# zx-SD-Card_SPI.net
KiCad netlist of a schematic drawn in Altium Designer
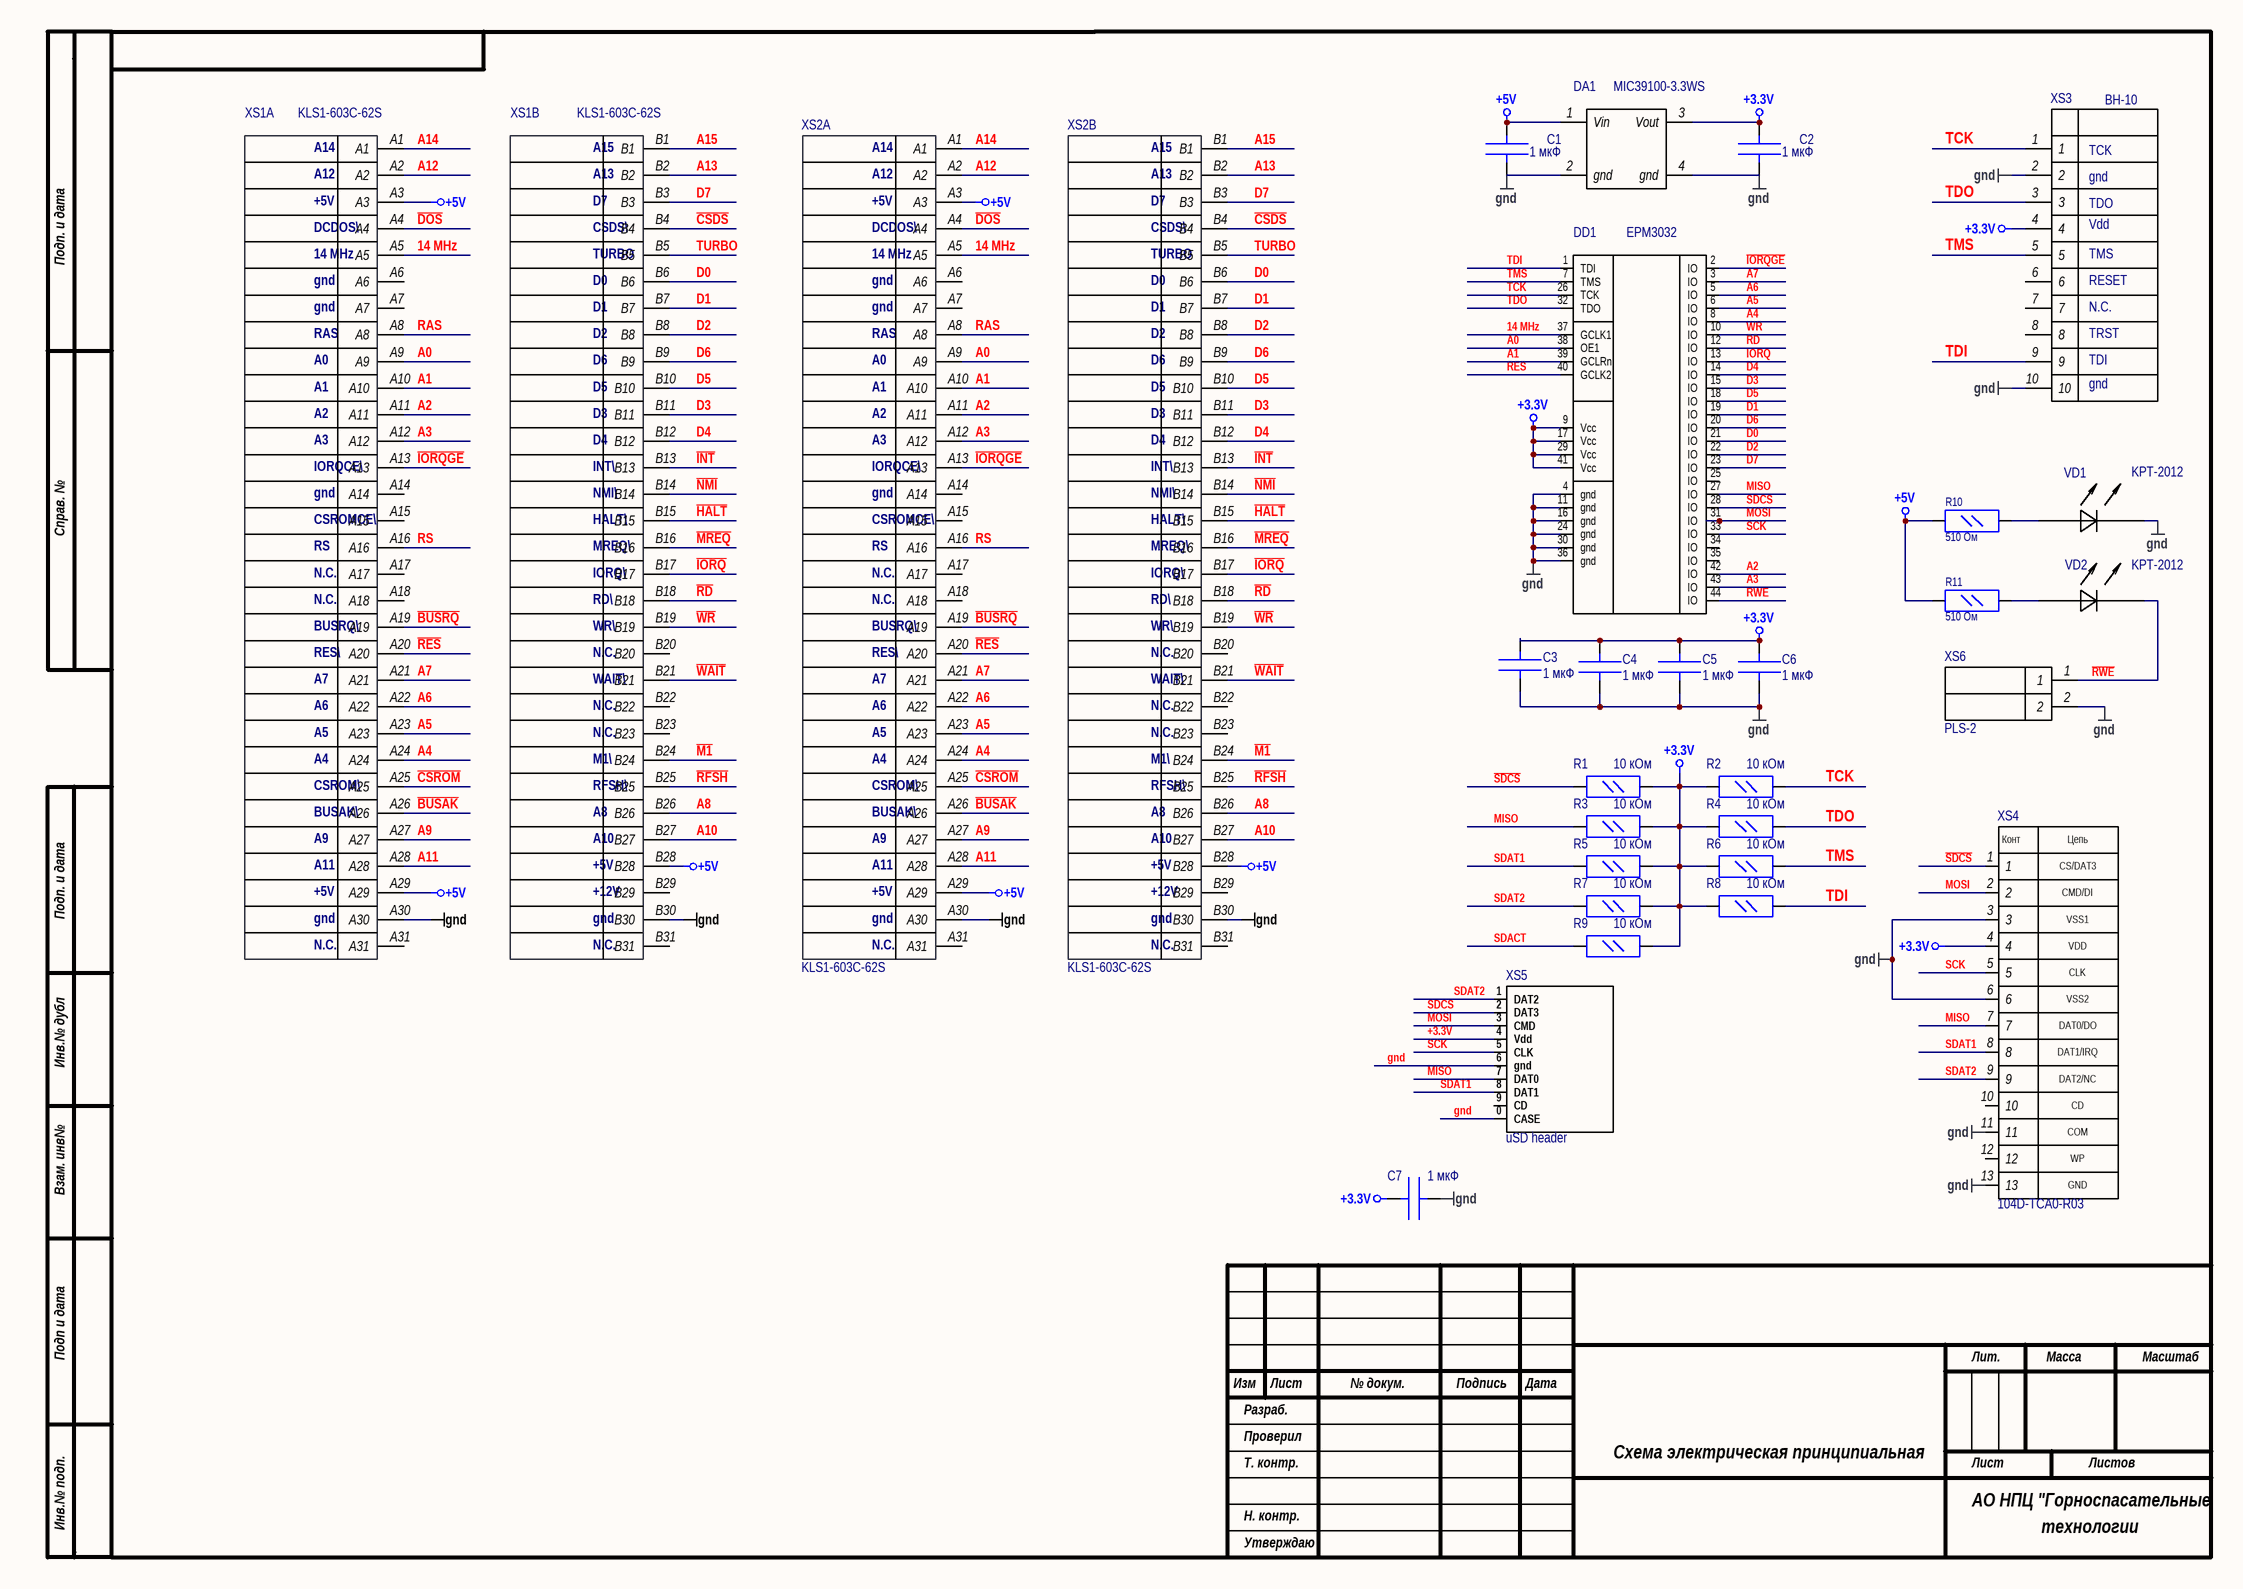
[diagram p0: zx-SD-Card_SPI.SchDoc]

(export (version "E")
  (design (tool "Eeschema 10.0.6"))
  (components
    (comp (ref "C1")
      (value "1 мкФ")
      (footprint "CAP C 3216 (1206) 1.9h")
      (description "Конденсатор не полярный")
      (fields (field (name "PART NUMBER") "CC1206KKX5R9BB105") (field (name "VOLTAGE") "50"))
      (libsource (lib "Capacitor_chip 1206$") (part "ЧИП-1206-X5R-1 мкФ 50В ±10%"))
    )
    (comp (ref "C2")
      (value "1 мкФ")
      (footprint "CAP C 3216 (1206) 1.9h")
      (description "Конденсатор не полярный")
      (fields (field (name "PART NUMBER") "CC1206KKX5R9BB105") (field (name "VOLTAGE") "50"))
      (libsource (lib "Capacitor_chip 1206$") (part "ЧИП-1206-X5R-1 мкФ 50В ±10%"))
    )
    (comp (ref "C3")
      (value "1 мкФ")
      (footprint "CAP C 2012 (0805) 1.45h")
      (description "Конденсатор не полярный")
      (fields (field (name "PART NUMBER") "CC0805KKX5R9BB105") (field (name "VOLTAGE") "50"))
      (libsource (lib "Capacitor_chip 0805$") (part "ЧИП-0805-X5R-1 мкФ 50В ±10%"))
    )
    (comp (ref "C4")
      (value "1 мкФ")
      (footprint "CAP C 2012 (0805) 1.45h")
      (description "Конденсатор не полярный")
      (fields (field (name "PART NUMBER") "CC0805KKX5R9BB105") (field (name "VOLTAGE") "50"))
      (libsource (lib "Capacitor_chip 0805$") (part "ЧИП-0805-X5R-1 мкФ 50В ±10%"))
    )
    (comp (ref "C5")
      (value "1 мкФ")
      (footprint "CAP C 2012 (0805) 1.45h")
      (description "Конденсатор не полярный")
      (fields (field (name "PART NUMBER") "CC0805KKX5R9BB105") (field (name "VOLTAGE") "50"))
      (libsource (lib "Capacitor_chip 0805$") (part "ЧИП-0805-X5R-1 мкФ 50В ±10%"))
    )
    (comp (ref "C6")
      (value "1 мкФ")
      (footprint "CAP C 2012 (0805) 1.45h")
      (description "Конденсатор не полярный")
      (fields (field (name "PART NUMBER") "CC0805KKX5R9BB105") (field (name "VOLTAGE") "50"))
      (libsource (lib "Capacitor_chip 0805$") (part "ЧИП-0805-X5R-1 мкФ 50В ±10%"))
    )
    (comp (ref "C7")
      (value "1 мкФ")
      (footprint "CAP C 2012 (0805) 1.45h")
      (description "Конденсатор не полярный")
      (fields (field (name "PART NUMBER") "CC0805KKX5R9BB105") (field (name "VOLTAGE") "50"))
      (libsource (lib "Capacitor_chip 0805$") (part "ЧИП-0805-X5R-1 мкФ 50В ±10%"))
    )
    (comp (ref "DA1")
      (value "MIC39100-3.3WS")
      (footprint "MIC39100-3.3WS")
      (description "LDO 3.3V 1A")
      (libsource (lib "ipa") (part "MIC39100-3.3WS"))
    )
    (comp (ref "DD1") (value "EPM3032") (footprint "ALTERA TQFP-44") (libsource (lib "gst") (part "EPM3032")))
    (comp (ref "R1")
      (value "10 кОм")
      (footprint "RES C 2012 (0805) 0.65h")
      (description "Резистор 0.125 Вт")
      (fields (field (name "PART NUMBER") "RC0805FR-0710KL") (field (name "TOLERANCE") "±1%"))
      (libsource (lib "Resistor_chip 0805$") (part "ЧИП-0805-10 кОм ±1%"))
    )
    (comp (ref "R2")
      (value "10 кОм")
      (footprint "RES C 2012 (0805) 0.65h")
      (description "Резистор 0.125 Вт")
      (fields (field (name "PART NUMBER") "RC0805FR-0710KL") (field (name "TOLERANCE") "±1%"))
      (libsource (lib "Resistor_chip 0805$") (part "ЧИП-0805-10 кОм ±1%"))
    )
    (comp (ref "R3")
      (value "10 кОм")
      (footprint "RES C 2012 (0805) 0.65h")
      (description "Резистор 0.125 Вт")
      (fields (field (name "PART NUMBER") "RC0805FR-0710KL") (field (name "TOLERANCE") "±1%"))
      (libsource (lib "Resistor_chip 0805$") (part "ЧИП-0805-10 кОм ±1%"))
    )
    (comp (ref "R4")
      (value "10 кОм")
      (footprint "RES C 2012 (0805) 0.65h")
      (description "Резистор 0.125 Вт")
      (fields (field (name "PART NUMBER") "RC0805FR-0710KL") (field (name "TOLERANCE") "±1%"))
      (libsource (lib "Resistor_chip 0805$") (part "ЧИП-0805-10 кОм ±1%"))
    )
    (comp (ref "R5")
      (value "10 кОм")
      (footprint "RES C 2012 (0805) 0.65h")
      (description "Резистор 0.125 Вт")
      (fields (field (name "PART NUMBER") "RC0805FR-0710KL") (field (name "TOLERANCE") "±1%"))
      (libsource (lib "Resistor_chip 0805$") (part "ЧИП-0805-10 кОм ±1%"))
    )
    (comp (ref "R6")
      (value "10 кОм")
      (footprint "RES C 2012 (0805) 0.65h")
      (description "Резистор 0.125 Вт")
      (fields (field (name "PART NUMBER") "RC0805FR-0710KL") (field (name "TOLERANCE") "±1%"))
      (libsource (lib "Resistor_chip 0805$") (part "ЧИП-0805-10 кОм ±1%"))
    )
    (comp (ref "R7")
      (value "10 кОм")
      (footprint "RES C 2012 (0805) 0.65h")
      (description "Резистор 0.125 Вт")
      (fields (field (name "PART NUMBER") "RC0805FR-0710KL") (field (name "TOLERANCE") "±1%"))
      (libsource (lib "Resistor_chip 0805$") (part "ЧИП-0805-10 кОм ±1%"))
    )
    (comp (ref "R8")
      (value "10 кОм")
      (footprint "RES C 2012 (0805) 0.65h")
      (description "Резистор 0.125 Вт")
      (fields (field (name "PART NUMBER") "RC0805FR-0710KL") (field (name "TOLERANCE") "±1%"))
      (libsource (lib "Resistor_chip 0805$") (part "ЧИП-0805-10 кОм ±1%"))
    )
    (comp (ref "R9")
      (value "10 кОм")
      (footprint "RES C 2012 (0805) 0.65h")
      (description "Резистор 0.125 Вт")
      (fields (field (name "PART NUMBER") "RC0805FR-0710KL") (field (name "TOLERANCE") "±1%"))
      (libsource (lib "Resistor_chip 0805$") (part "ЧИП-0805-10 кОм ±1%"))
    )
    (comp (ref "R10")
      (value "510 Ом")
      (footprint "RES C 2012 (0805) 0.65h")
      (description "Резистор 0.125 Вт")
      (fields (field (name "PART NUMBER") "RC0805JR-07510RL") (field (name "TOLERANCE") "±5%"))
      (libsource (lib "Resistor_chip 0805$") (part "ЧИП-0805-510 Ом ±5%"))
    )
    (comp (ref "R11")
      (value "510 Ом")
      (footprint "RES C 2012 (0805) 0.65h")
      (description "Резистор 0.125 Вт")
      (fields (field (name "PART NUMBER") "RC0805JR-07510RL") (field (name "TOLERANCE") "±5%"))
      (libsource (lib "Resistor_chip 0805$") (part "ЧИП-0805-510 Ом ±5%"))
    )
    (comp (ref "VD1") (value "KPT-2012") (footprint "KPT-2012") (libsource (lib "ipa") (part "KPT-2012")))
    (comp (ref "VD2") (value "KPT-2012") (footprint "KPT-2012") (libsource (lib "ipa") (part "KPT-2012")))
    (comp (ref "XS1")
      (value "KLS1-603C-62S")
      (footprint "KLS1-603 ISA")
      (libsource (lib "gst") (part "KLS1-603C-64S"))
    )
    (comp (ref "XS2")
      (value "KLS1-603C-62S")
      (footprint "KLS1-603C-64S")
      (libsource (lib "gst") (part "KLS1-603C-64S"))
    )
    (comp (ref "XS3") (value "BH-10") (footprint "BH-10") (libsource (lib "ipa") (part "AVR_ISP_JTAG")))
    (comp (ref "XS4")
      (value "104D-TCA0-R03")
      (footprint "104D-TCA0-R03")
      (fields (field (name "MANUFACTURER") "Attend technology"))
      (libsource (lib "Connector$") (part "104D-TCA0-R03"))
    )
    (comp (ref "XS5")
      (value "uSD header")
      (footprint "uSD")
      (description "uSD")
      (libsource (lib "gst") (part "uSD"))
    )
    (comp (ref "XS6") (value "PLS-2") (footprint "PLS-2") (libsource (lib "ipa") (part "PLS-2")))
  )
  (nets
    (net (code "1") (name "+3.3V") (class "Default")
      (node (ref "C2") (pin "2") (pinfunction "2_2") (pintype "passive"))
      (node (ref "C3") (pin "1") (pinfunction "1_1") (pintype "passive"))
      (node (ref "C4") (pin "1") (pinfunction "1_1") (pintype "passive"))
      (node (ref "C5") (pin "1") (pinfunction "1_1") (pintype "passive"))
      (node (ref "C6") (pin "1") (pinfunction "1_1") (pintype "passive"))
      (node (ref "C7") (pin "1") (pinfunction "1_1") (pintype "passive"))
      (node (ref "DA1") (pin "3") (pinfunction "Vout_3") (pintype "passive"))
      (node (ref "DD1") (pin "17") (pinfunction "Vcc_17") (pintype "passive"))
      (node (ref "DD1") (pin "29") (pinfunction "Vcc_29") (pintype "passive"))
      (node (ref "DD1") (pin "41") (pinfunction "Vcc_41") (pintype "passive"))
      (node (ref "DD1") (pin "9") (pinfunction "Vcc_9") (pintype "passive"))
      (node (ref "R1") (pin "2") (pinfunction "2_2") (pintype "passive"))
      (node (ref "R2") (pin "1") (pinfunction "1_1") (pintype "passive"))
      (node (ref "R3") (pin "2") (pinfunction "2_2") (pintype "passive"))
      (node (ref "R4") (pin "1") (pinfunction "1_1") (pintype "passive"))
      (node (ref "R5") (pin "2") (pinfunction "2_2") (pintype "passive"))
      (node (ref "R6") (pin "1") (pinfunction "1_1") (pintype "passive"))
      (node (ref "R7") (pin "2") (pinfunction "2_2") (pintype "passive"))
      (node (ref "R8") (pin "1") (pinfunction "1_1") (pintype "passive"))
      (node (ref "R9") (pin "2") (pinfunction "2_2") (pintype "passive"))
      (node (ref "XS3") (pin "4") (pinfunction "4_4") (pintype "passive"))
      (node (ref "XS4") (pin "4") (pinfunction "4_4") (pintype "passive"))
      (node (ref "XS5") (pin "4") (pinfunction "Vdd_4") (pintype "passive"))
    )
    (net (code "2") (name "+5V") (class "Default")
      (node (ref "C1") (pin "2") (pinfunction "2_2") (pintype "passive"))
      (node (ref "DA1") (pin "1") (pinfunction "Vin_1") (pintype "passive"))
      (node (ref "R10") (pin "1") (pinfunction "1_1") (pintype "passive"))
      (node (ref "R11") (pin "1") (pinfunction "1_1") (pintype "passive"))
      (node (ref "XS1") (pin "A29") (pinfunction "A29_A29") (pintype "passive"))
      (node (ref "XS1") (pin "A3") (pinfunction "A3_A3") (pintype "passive"))
      (node (ref "XS1") (pin "B28") (pinfunction "B28_B28") (pintype "passive"))
      (node (ref "XS2") (pin "A29") (pinfunction "A29_A29") (pintype "passive"))
      (node (ref "XS2") (pin "A3") (pinfunction "A3_A3") (pintype "passive"))
      (node (ref "XS2") (pin "B28") (pinfunction "B28_B28") (pintype "passive"))
    )
    (net (code "3") (name "/14 MHz") (class "Default")
      (node (ref "DD1") (pin "37") (pinfunction "GCLK1_37") (pintype "passive"))
      (node (ref "XS1") (pin "A5") (pinfunction "A5_A5") (pintype "passive"))
      (node (ref "XS2") (pin "A5") (pinfunction "A5_A5") (pintype "passive"))
    )
    (net (code "4") (name "/A0") (class "Default")
      (node (ref "DD1") (pin "38") (pinfunction "OE1_38") (pintype "passive"))
      (node (ref "XS1") (pin "A9") (pinfunction "A9_A9") (pintype "passive"))
      (node (ref "XS2") (pin "A9") (pinfunction "A9_A9") (pintype "passive"))
    )
    (net (code "5") (name "/A1") (class "Default")
      (node (ref "DD1") (pin "39") (pinfunction "GCLRn_39") (pintype "passive"))
      (node (ref "XS1") (pin "A10") (pinfunction "A10_A10") (pintype "passive"))
      (node (ref "XS2") (pin "A10") (pinfunction "A10_A10") (pintype "passive"))
    )
    (net (code "6") (name "/A2") (class "Default")
      (node (ref "DD1") (pin "42") (pinfunction "IO_42") (pintype "passive"))
      (node (ref "XS1") (pin "A11") (pinfunction "A11_A11") (pintype "passive"))
      (node (ref "XS2") (pin "A11") (pinfunction "A11_A11") (pintype "passive"))
    )
    (net (code "7") (name "/A3") (class "Default")
      (node (ref "DD1") (pin "43") (pinfunction "IO_43") (pintype "passive"))
      (node (ref "XS1") (pin "A12") (pinfunction "A12_A12") (pintype "passive"))
      (node (ref "XS2") (pin "A12") (pinfunction "A12_A12") (pintype "passive"))
    )
    (net (code "8") (name "/A4") (class "Default")
      (node (ref "DD1") (pin "8") (pinfunction "IO_8") (pintype "passive"))
      (node (ref "XS1") (pin "A24") (pinfunction "A24_A24") (pintype "passive"))
      (node (ref "XS2") (pin "A24") (pinfunction "A24_A24") (pintype "passive"))
    )
    (net (code "9") (name "/A5") (class "Default")
      (node (ref "DD1") (pin "6") (pinfunction "IO_6") (pintype "passive"))
      (node (ref "XS1") (pin "A23") (pinfunction "A23_A23") (pintype "passive"))
      (node (ref "XS2") (pin "A23") (pinfunction "A23_A23") (pintype "passive"))
    )
    (net (code "10") (name "/A6") (class "Default")
      (node (ref "DD1") (pin "5") (pinfunction "IO_5") (pintype "passive"))
      (node (ref "XS1") (pin "A22") (pinfunction "A22_A22") (pintype "passive"))
      (node (ref "XS2") (pin "A22") (pinfunction "A22_A22") (pintype "passive"))
    )
    (net (code "11") (name "/A7") (class "Default")
      (node (ref "DD1") (pin "3") (pinfunction "IO_3") (pintype "passive"))
      (node (ref "XS1") (pin "A21") (pinfunction "A21_A21") (pintype "passive"))
      (node (ref "XS2") (pin "A21") (pinfunction "A21_A21") (pintype "passive"))
    )
    (net (code "12") (name "/A8") (class "Default")
      (node (ref "XS1") (pin "B26") (pinfunction "B26_B26") (pintype "passive"))
      (node (ref "XS2") (pin "B26") (pinfunction "B26_B26") (pintype "passive"))
    )
    (net (code "13") (name "/A9") (class "Default")
      (node (ref "XS1") (pin "A27") (pinfunction "A27_A27") (pintype "passive"))
      (node (ref "XS2") (pin "A27") (pinfunction "A27_A27") (pintype "passive"))
    )
    (net (code "14") (name "/A10") (class "Default")
      (node (ref "XS1") (pin "B27") (pinfunction "B27_B27") (pintype "passive"))
      (node (ref "XS2") (pin "B27") (pinfunction "B27_B27") (pintype "passive"))
    )
    (net (code "15") (name "/A11") (class "Default")
      (node (ref "XS1") (pin "A28") (pinfunction "A28_A28") (pintype "passive"))
      (node (ref "XS2") (pin "A28") (pinfunction "A28_A28") (pintype "passive"))
    )
    (net (code "16") (name "/A12") (class "Default")
      (node (ref "XS1") (pin "A2") (pinfunction "A2_A2") (pintype "passive"))
      (node (ref "XS2") (pin "A2") (pinfunction "A2_A2") (pintype "passive"))
    )
    (net (code "17") (name "/A13") (class "Default")
      (node (ref "XS1") (pin "B2") (pinfunction "B2_B2") (pintype "passive"))
      (node (ref "XS2") (pin "B2") (pinfunction "B2_B2") (pintype "passive"))
    )
    (net (code "18") (name "/A14") (class "Default")
      (node (ref "XS1") (pin "A1") (pinfunction "A1_A1") (pintype "passive"))
      (node (ref "XS2") (pin "A1") (pinfunction "A1_A1") (pintype "passive"))
    )
    (net (code "19") (name "/A15") (class "Default")
      (node (ref "XS1") (pin "B1") (pinfunction "B1_B1") (pintype "passive"))
      (node (ref "XS2") (pin "B1") (pinfunction "B1_B1") (pintype "passive"))
    )
    (net (code "20") (name "/D0") (class "Default")
      (node (ref "DD1") (pin "21") (pinfunction "IO_21") (pintype "passive"))
      (node (ref "XS1") (pin "B6") (pinfunction "B6_B6") (pintype "passive"))
      (node (ref "XS2") (pin "B6") (pinfunction "B6_B6") (pintype "passive"))
    )
    (net (code "21") (name "/D1") (class "Default")
      (node (ref "DD1") (pin "19") (pinfunction "IO_19") (pintype "passive"))
      (node (ref "XS1") (pin "B7") (pinfunction "B7_B7") (pintype "passive"))
      (node (ref "XS2") (pin "B7") (pinfunction "B7_B7") (pintype "passive"))
    )
    (net (code "22") (name "/D2") (class "Default")
      (node (ref "DD1") (pin "22") (pinfunction "IO_22") (pintype "passive"))
      (node (ref "XS1") (pin "B8") (pinfunction "B8_B8") (pintype "passive"))
      (node (ref "XS2") (pin "B8") (pinfunction "B8_B8") (pintype "passive"))
    )
    (net (code "23") (name "/D3") (class "Default")
      (node (ref "DD1") (pin "15") (pinfunction "IO_15") (pintype "passive"))
      (node (ref "XS1") (pin "B11") (pinfunction "B11_B11") (pintype "passive"))
      (node (ref "XS2") (pin "B11") (pinfunction "B11_B11") (pintype "passive"))
    )
    (net (code "24") (name "/D4") (class "Default")
      (node (ref "DD1") (pin "14") (pinfunction "IO_14") (pintype "passive"))
      (node (ref "XS1") (pin "B12") (pinfunction "B12_B12") (pintype "passive"))
      (node (ref "XS2") (pin "B12") (pinfunction "B12_B12") (pintype "passive"))
    )
    (net (code "25") (name "/D5") (class "Default")
      (node (ref "DD1") (pin "18") (pinfunction "IO_18") (pintype "passive"))
      (node (ref "XS1") (pin "B10") (pinfunction "B10_B10") (pintype "passive"))
      (node (ref "XS2") (pin "B10") (pinfunction "B10_B10") (pintype "passive"))
    )
    (net (code "26") (name "/D6") (class "Default")
      (node (ref "DD1") (pin "20") (pinfunction "IO_20") (pintype "passive"))
      (node (ref "XS1") (pin "B9") (pinfunction "B9_B9") (pintype "passive"))
      (node (ref "XS2") (pin "B9") (pinfunction "B9_B9") (pintype "passive"))
    )
    (net (code "27") (name "/D7") (class "Default")
      (node (ref "DD1") (pin "23") (pinfunction "IO_23") (pintype "passive"))
      (node (ref "XS1") (pin "B3") (pinfunction "B3_B3") (pintype "passive"))
      (node (ref "XS2") (pin "B3") (pinfunction "B3_B3") (pintype "passive"))
    )
    (net (code "28") (name "/MISO") (class "Default")
      (node (ref "DD1") (pin "27") (pinfunction "IO_27") (pintype "passive"))
      (node (ref "R3") (pin "1") (pinfunction "1_1") (pintype "passive"))
      (node (ref "XS4") (pin "7") (pinfunction "7_7") (pintype "passive"))
      (node (ref "XS5") (pin "7") (pinfunction "DAT0_7") (pintype "passive"))
    )
    (net (code "29") (name "/MOSI") (class "Default")
      (node (ref "DD1") (pin "31") (pinfunction "IO_31") (pintype "passive"))
      (node (ref "XS4") (pin "2") (pinfunction "2_2") (pintype "passive"))
      (node (ref "XS5") (pin "3") (pinfunction "CMD_3") (pintype "passive"))
    )
    (net (code "30") (name "/RAS") (class "Default")
      (node (ref "XS1") (pin "A8") (pinfunction "A8_A8") (pintype "passive"))
      (node (ref "XS2") (pin "A8") (pinfunction "A8_A8") (pintype "passive"))
    )
    (net (code "31") (name "/RS") (class "Default")
      (node (ref "XS1") (pin "A16") (pinfunction "A16_A16") (pintype "passive"))
      (node (ref "XS2") (pin "A16") (pinfunction "A16_A16") (pintype "passive"))
    )
    (net (code "32") (name "/SCK") (class "Default")
      (node (ref "DD1") (pin "33") (pinfunction "IO_33") (pintype "passive"))
      (node (ref "XS4") (pin "5") (pinfunction "5_5") (pintype "passive"))
      (node (ref "XS5") (pin "5") (pinfunction "CLK_5") (pintype "passive"))
    )
    (net (code "33") (name "/SDACT") (class "Default")
      (node (ref "R9") (pin "1") (pinfunction "1_1") (pintype "passive"))
    )
    (net (code "34") (name "/SDAT1") (class "Default")
      (node (ref "R5") (pin "1") (pinfunction "1_1") (pintype "passive"))
      (node (ref "XS4") (pin "8") (pinfunction "8_8") (pintype "passive"))
      (node (ref "XS5") (pin "8") (pinfunction "DAT1_8") (pintype "passive"))
    )
    (net (code "35") (name "/SDAT2") (class "Default")
      (node (ref "R7") (pin "1") (pinfunction "1_1") (pintype "passive"))
      (node (ref "XS4") (pin "9") (pinfunction "9_9") (pintype "passive"))
      (node (ref "XS5") (pin "1") (pinfunction "DAT2_1") (pintype "passive"))
    )
    (net (code "36") (name "/TCK") (class "Default")
      (node (ref "DD1") (pin "26") (pinfunction "TCK_26") (pintype "passive"))
      (node (ref "R2") (pin "2") (pinfunction "2_2") (pintype "passive"))
      (node (ref "XS3") (pin "1") (pinfunction "1_1") (pintype "passive"))
    )
    (net (code "37") (name "/TDI") (class "Default")
      (node (ref "DD1") (pin "1") (pinfunction "TDI_1") (pintype "passive"))
      (node (ref "R8") (pin "2") (pinfunction "2_2") (pintype "passive"))
      (node (ref "XS3") (pin "9") (pinfunction "9_9") (pintype "passive"))
    )
    (net (code "38") (name "/TDO") (class "Default")
      (node (ref "DD1") (pin "32") (pinfunction "TDO_32") (pintype "passive"))
      (node (ref "R4") (pin "2") (pinfunction "2_2") (pintype "passive"))
      (node (ref "XS3") (pin "3") (pinfunction "3_3") (pintype "passive"))
    )
    (net (code "39") (name "/TMS") (class "Default")
      (node (ref "DD1") (pin "7") (pinfunction "TMS_7") (pintype "passive"))
      (node (ref "R6") (pin "2") (pinfunction "2_2") (pintype "passive"))
      (node (ref "XS3") (pin "5") (pinfunction "5_5") (pintype "passive"))
    )
    (net (code "40") (name "/TURBO") (class "Default")
      (node (ref "XS1") (pin "B5") (pinfunction "B5_B5") (pintype "passive"))
      (node (ref "XS2") (pin "B5") (pinfunction "B5_B5") (pintype "passive"))
    )
    (net (code "41") (name "/~{BUSAK}") (class "Default")
      (node (ref "XS1") (pin "A26") (pinfunction "A26_A26") (pintype "passive"))
      (node (ref "XS2") (pin "A26") (pinfunction "A26_A26") (pintype "passive"))
    )
    (net (code "42") (name "/~{BUSRQ}") (class "Default")
      (node (ref "XS1") (pin "A19") (pinfunction "A19_A19") (pintype "passive"))
      (node (ref "XS2") (pin "A19") (pinfunction "A19_A19") (pintype "passive"))
    )
    (net (code "43") (name "/~{CSDS}") (class "Default")
      (node (ref "XS1") (pin "B4") (pinfunction "B4_B4") (pintype "passive"))
      (node (ref "XS2") (pin "B4") (pinfunction "B4_B4") (pintype "passive"))
    )
    (net (code "44") (name "/~{CSROM}") (class "Default")
      (node (ref "XS1") (pin "A25") (pinfunction "A25_A25") (pintype "passive"))
      (node (ref "XS2") (pin "A25") (pinfunction "A25_A25") (pintype "passive"))
    )
    (net (code "45") (name "/~{DOS}") (class "Default")
      (node (ref "XS1") (pin "A4") (pinfunction "A4_A4") (pintype "passive"))
      (node (ref "XS2") (pin "A4") (pinfunction "A4_A4") (pintype "passive"))
    )
    (net (code "46") (name "/~{HALT}") (class "Default")
      (node (ref "XS1") (pin "B15") (pinfunction "B15_B15") (pintype "passive"))
      (node (ref "XS2") (pin "B15") (pinfunction "B15_B15") (pintype "passive"))
    )
    (net (code "47") (name "/~{INT}") (class "Default")
      (node (ref "XS1") (pin "B13") (pinfunction "B13_B13") (pintype "passive"))
      (node (ref "XS2") (pin "B13") (pinfunction "B13_B13") (pintype "passive"))
    )
    (net (code "48") (name "/~{IORQGE}") (class "Default")
      (node (ref "DD1") (pin "2") (pinfunction "IO_2") (pintype "passive"))
      (node (ref "XS1") (pin "A13") (pinfunction "A13_A13") (pintype "passive"))
      (node (ref "XS2") (pin "A13") (pinfunction "A13_A13") (pintype "passive"))
    )
    (net (code "49") (name "/~{IORQ}") (class "Default")
      (node (ref "DD1") (pin "13") (pinfunction "IO_13") (pintype "passive"))
      (node (ref "XS1") (pin "B17") (pinfunction "B17_B17") (pintype "passive"))
      (node (ref "XS2") (pin "B17") (pinfunction "B17_B17") (pintype "passive"))
    )
    (net (code "50") (name "/~{M1}") (class "Default")
      (node (ref "XS1") (pin "B24") (pinfunction "B24_B24") (pintype "passive"))
      (node (ref "XS2") (pin "B24") (pinfunction "B24_B24") (pintype "passive"))
    )
    (net (code "51") (name "/~{MREQ}") (class "Default")
      (node (ref "XS1") (pin "B16") (pinfunction "B16_B16") (pintype "passive"))
      (node (ref "XS2") (pin "B16") (pinfunction "B16_B16") (pintype "passive"))
    )
    (net (code "52") (name "/~{NMI}") (class "Default")
      (node (ref "XS1") (pin "B14") (pinfunction "B14_B14") (pintype "passive"))
      (node (ref "XS2") (pin "B14") (pinfunction "B14_B14") (pintype "passive"))
    )
    (net (code "53") (name "/~{RD}") (class "Default")
      (node (ref "DD1") (pin "12") (pinfunction "IO_12") (pintype "passive"))
      (node (ref "XS1") (pin "B18") (pinfunction "B18_B18") (pintype "passive"))
      (node (ref "XS2") (pin "B18") (pinfunction "B18_B18") (pintype "passive"))
    )
    (net (code "54") (name "/~{RES}") (class "Default")
      (node (ref "DD1") (pin "40") (pinfunction "GCLK2_40") (pintype "passive"))
      (node (ref "XS1") (pin "A20") (pinfunction "A20_A20") (pintype "passive"))
      (node (ref "XS2") (pin "A20") (pinfunction "A20_A20") (pintype "passive"))
    )
    (net (code "55") (name "/~{RFSH}") (class "Default")
      (node (ref "XS1") (pin "B25") (pinfunction "B25_B25") (pintype "passive"))
      (node (ref "XS2") (pin "B25") (pinfunction "B25_B25") (pintype "passive"))
    )
    (net (code "56") (name "/~{RWE}") (class "Default")
      (node (ref "DD1") (pin "44") (pinfunction "IO_44") (pintype "passive"))
      (node (ref "VD2") (pin "2") (pinfunction "2_2") (pintype "passive"))
      (node (ref "XS6") (pin "1") (pinfunction "1_1") (pintype "passive"))
    )
    (net (code "57") (name "/~{SDCS}") (class "Default")
      (node (ref "DD1") (pin "28") (pinfunction "IO_28") (pintype "passive"))
      (node (ref "R1") (pin "1") (pinfunction "1_1") (pintype "passive"))
      (node (ref "XS4") (pin "1") (pinfunction "1_1") (pintype "passive"))
      (node (ref "XS5") (pin "2") (pinfunction "DAT3_2") (pintype "passive"))
    )
    (net (code "58") (name "/~{WAIT}") (class "Default")
      (node (ref "XS1") (pin "B21") (pinfunction "B21_B21") (pintype "passive"))
      (node (ref "XS2") (pin "B21") (pinfunction "B21_B21") (pintype "passive"))
    )
    (net (code "59") (name "/~{WR}") (class "Default")
      (node (ref "DD1") (pin "10") (pinfunction "IO_10") (pintype "passive"))
      (node (ref "XS1") (pin "B19") (pinfunction "B19_B19") (pintype "passive"))
      (node (ref "XS2") (pin "B19") (pinfunction "B19_B19") (pintype "passive"))
    )
    (net (code "60") (name "Net-(R10-Pad2)") (class "Default")
      (node (ref "R10") (pin "2") (pinfunction "2_2") (pintype "passive"))
      (node (ref "VD1") (pin "1") (pinfunction "1_1") (pintype "passive"))
    )
    (net (code "61") (name "Net-(R11-Pad2)") (class "Default")
      (node (ref "R11") (pin "2") (pinfunction "2_2") (pintype "passive"))
      (node (ref "VD2") (pin "1") (pinfunction "1_1") (pintype "passive"))
    )
    (net (code "62") (name "gnd") (class "Default")
      (node (ref "C1") (pin "1") (pinfunction "1_1") (pintype "passive"))
      (node (ref "C2") (pin "1") (pinfunction "1_1") (pintype "passive"))
      (node (ref "C3") (pin "2") (pinfunction "2_2") (pintype "passive"))
      (node (ref "C4") (pin "2") (pinfunction "2_2") (pintype "passive"))
      (node (ref "C5") (pin "2") (pinfunction "2_2") (pintype "passive"))
      (node (ref "C6") (pin "2") (pinfunction "2_2") (pintype "passive"))
      (node (ref "C7") (pin "2") (pinfunction "2_2") (pintype "passive"))
      (node (ref "DA1") (pin "2") (pinfunction "gnd_2") (pintype "passive"))
      (node (ref "DA1") (pin "4") (pinfunction "gnd_4") (pintype "passive"))
      (node (ref "DD1") (pin "11") (pinfunction "gnd_11") (pintype "passive"))
      (node (ref "DD1") (pin "16") (pinfunction "gnd_16") (pintype "passive"))
      (node (ref "DD1") (pin "24") (pinfunction "gnd_24") (pintype "passive"))
      (node (ref "DD1") (pin "30") (pinfunction "gnd_30") (pintype "passive"))
      (node (ref "DD1") (pin "36") (pinfunction "gnd_36") (pintype "passive"))
      (node (ref "DD1") (pin "4") (pinfunction "gnd_4") (pintype "passive"))
      (node (ref "VD1") (pin "2") (pinfunction "2_2") (pintype "passive"))
      (node (ref "XS1") (pin "A30") (pinfunction "A30_A30") (pintype "passive"))
      (node (ref "XS1") (pin "B30") (pinfunction "B30_B30") (pintype "passive"))
      (node (ref "XS2") (pin "A30") (pinfunction "A30_A30") (pintype "passive"))
      (node (ref "XS2") (pin "B30") (pinfunction "B30_B30") (pintype "passive"))
      (node (ref "XS3") (pin "10") (pinfunction "10_10") (pintype "passive"))
      (node (ref "XS3") (pin "2") (pinfunction "2_2") (pintype "passive"))
      (node (ref "XS4") (pin "11") (pinfunction "11_11") (pintype "passive"))
      (node (ref "XS4") (pin "13") (pinfunction "13_13") (pintype "passive"))
      (node (ref "XS4") (pin "3") (pinfunction "3_3") (pintype "passive"))
      (node (ref "XS4") (pin "6") (pinfunction "6_6") (pintype "passive"))
      (node (ref "XS5") (pin "0") (pinfunction "CASE_0") (pintype "passive"))
      (node (ref "XS5") (pin "6") (pinfunction "gnd_6") (pintype "passive"))
      (node (ref "XS6") (pin "2") (pinfunction "2_2") (pintype "passive"))
    )
    (net (code "63") (name "unconnected-(DD1-IO-Pad25)") (class "Default")
      (node (ref "DD1") (pin "25") (pinfunction "IO_25") (pintype "passive"))
    )
    (net (code "64") (name "unconnected-(DD1-IO-Pad34)") (class "Default")
      (node (ref "DD1") (pin "34") (pinfunction "IO_34") (pintype "passive"))
    )
    (net (code "65") (name "unconnected-(DD1-IO-Pad35)") (class "Default")
      (node (ref "DD1") (pin "35") (pinfunction "IO_35") (pintype "passive"))
    )
    (net (code "66") (name "unconnected-(XS1-PadA6)") (class "Default")
      (node (ref "XS1") (pin "A6") (pinfunction "A6_A6") (pintype "passive"))
    )
    (net (code "67") (name "unconnected-(XS1-PadA7)") (class "Default")
      (node (ref "XS1") (pin "A7") (pinfunction "A7_A7") (pintype "passive"))
    )
    (net (code "68") (name "unconnected-(XS1-PadA14)") (class "Default")
      (node (ref "XS1") (pin "A14") (pinfunction "A14_A14") (pintype "passive"))
    )
    (net (code "69") (name "unconnected-(XS1-PadA15)") (class "Default")
      (node (ref "XS1") (pin "A15") (pinfunction "A15_A15") (pintype "passive"))
    )
    (net (code "70") (name "unconnected-(XS1-PadA17)") (class "Default")
      (node (ref "XS1") (pin "A17") (pinfunction "A17_A17") (pintype "passive"))
    )
    (net (code "71") (name "unconnected-(XS1-PadA18)") (class "Default")
      (node (ref "XS1") (pin "A18") (pinfunction "A18_A18") (pintype "passive"))
    )
    (net (code "72") (name "unconnected-(XS1-PadA31)") (class "Default")
      (node (ref "XS1") (pin "A31") (pinfunction "A31_A31") (pintype "passive"))
    )
    (net (code "73") (name "unconnected-(XS1-PadB20)") (class "Default")
      (node (ref "XS1") (pin "B20") (pinfunction "B20_B20") (pintype "passive"))
    )
    (net (code "74") (name "unconnected-(XS1-PadB22)") (class "Default")
      (node (ref "XS1") (pin "B22") (pinfunction "B22_B22") (pintype "passive"))
    )
    (net (code "75") (name "unconnected-(XS1-PadB23)") (class "Default")
      (node (ref "XS1") (pin "B23") (pinfunction "B23_B23") (pintype "passive"))
    )
    (net (code "76") (name "unconnected-(XS1-PadB29)") (class "Default")
      (node (ref "XS1") (pin "B29") (pinfunction "B29_B29") (pintype "passive"))
    )
    (net (code "77") (name "unconnected-(XS1-PadB31)") (class "Default")
      (node (ref "XS1") (pin "B31") (pinfunction "B31_B31") (pintype "passive"))
    )
    (net (code "78") (name "unconnected-(XS2-PadA6)") (class "Default")
      (node (ref "XS2") (pin "A6") (pinfunction "A6_A6") (pintype "passive"))
    )
    (net (code "79") (name "unconnected-(XS2-PadA7)") (class "Default")
      (node (ref "XS2") (pin "A7") (pinfunction "A7_A7") (pintype "passive"))
    )
    (net (code "80") (name "unconnected-(XS2-PadA14)") (class "Default")
      (node (ref "XS2") (pin "A14") (pinfunction "A14_A14") (pintype "passive"))
    )
    (net (code "81") (name "unconnected-(XS2-PadA15)") (class "Default")
      (node (ref "XS2") (pin "A15") (pinfunction "A15_A15") (pintype "passive"))
    )
    (net (code "82") (name "unconnected-(XS2-PadA17)") (class "Default")
      (node (ref "XS2") (pin "A17") (pinfunction "A17_A17") (pintype "passive"))
    )
    (net (code "83") (name "unconnected-(XS2-PadA18)") (class "Default")
      (node (ref "XS2") (pin "A18") (pinfunction "A18_A18") (pintype "passive"))
    )
    (net (code "84") (name "unconnected-(XS2-PadA31)") (class "Default")
      (node (ref "XS2") (pin "A31") (pinfunction "A31_A31") (pintype "passive"))
    )
    (net (code "85") (name "unconnected-(XS2-PadB20)") (class "Default")
      (node (ref "XS2") (pin "B20") (pinfunction "B20_B20") (pintype "passive"))
    )
    (net (code "86") (name "unconnected-(XS2-PadB22)") (class "Default")
      (node (ref "XS2") (pin "B22") (pinfunction "B22_B22") (pintype "passive"))
    )
    (net (code "87") (name "unconnected-(XS2-PadB23)") (class "Default")
      (node (ref "XS2") (pin "B23") (pinfunction "B23_B23") (pintype "passive"))
    )
    (net (code "88") (name "unconnected-(XS2-PadB29)") (class "Default")
      (node (ref "XS2") (pin "B29") (pinfunction "B29_B29") (pintype "passive"))
    )
    (net (code "89") (name "unconnected-(XS2-PadB31)") (class "Default")
      (node (ref "XS2") (pin "B31") (pinfunction "B31_B31") (pintype "passive"))
    )
    (net (code "90") (name "unconnected-(XS3-Pad6)") (class "Default")
      (node (ref "XS3") (pin "6") (pinfunction "6_6") (pintype "passive"))
    )
    (net (code "91") (name "unconnected-(XS3-Pad7)") (class "Default")
      (node (ref "XS3") (pin "7") (pinfunction "7_7") (pintype "passive"))
    )
    (net (code "92") (name "unconnected-(XS3-Pad8)") (class "Default")
      (node (ref "XS3") (pin "8") (pinfunction "8_8") (pintype "passive"))
    )
    (net (code "93") (name "unconnected-(XS4-Pad10)") (class "Default")
      (node (ref "XS4") (pin "10") (pinfunction "10_10") (pintype "passive"))
    )
    (net (code "94") (name "unconnected-(XS4-Pad12)") (class "Default")
      (node (ref "XS4") (pin "12") (pinfunction "12_12") (pintype "passive"))
    )
    (net (code "95") (name "unconnected-(XS5-CD-Pad9)") (class "Default")
      (node (ref "XS5") (pin "9") (pinfunction "CD_9") (pintype "passive"))
    )
  )
)
